# MySens-GWeasySensRS485-V01-045.net
KiCad netlist of a schematic drawn in EAGLE
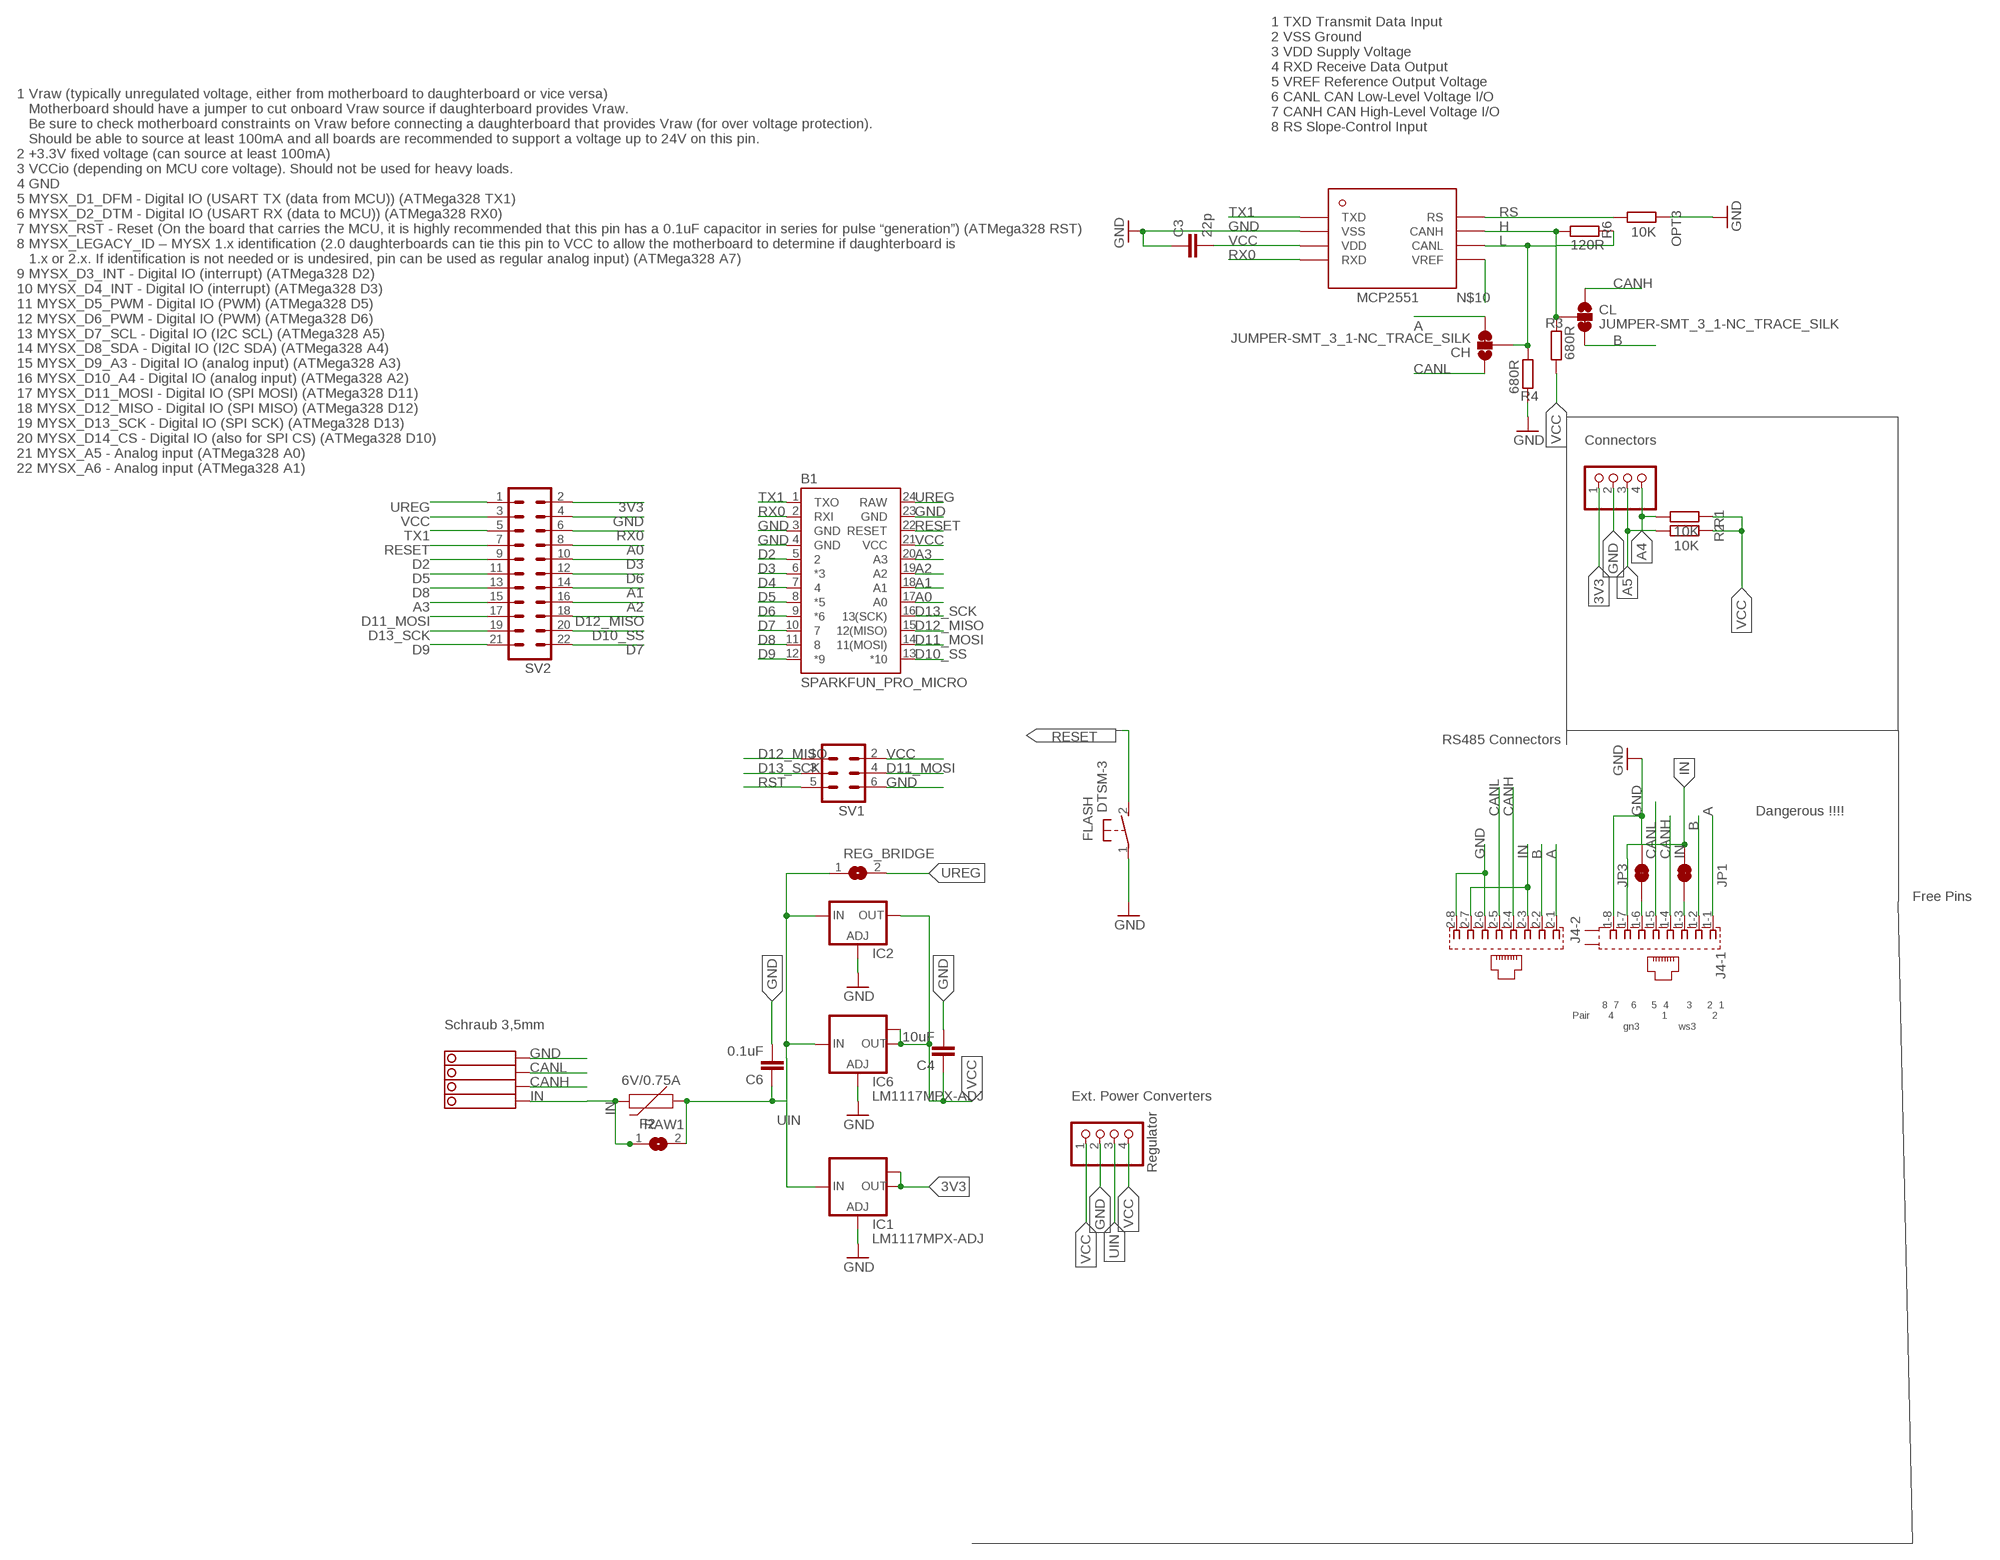
[diagram p0: schematic, sheet 1]

(export (version "E")
  (design (tool "Eeschema 10.0.6"))
  (components
    (comp (ref "B1")
      (value "SPARKFUN_PRO_MICRO")
      (footprint "eagle-import:SPARKFUN_PRO_MICRO")
      (libsource (lib "eagle-import") (part "SPARKFUN_PRO_MICRO"))
    )
    (comp (ref "C3")
      (value "22p")
      (footprint "eagle-import:C0805")
      (libsource (lib "eagle-import") (part "C-EUC0805"))
    )
    (comp (ref "C4")
      (value "10uF")
      (footprint "eagle-import:C1210")
      (libsource (lib "eagle-import") (part "C-EUC1210"))
    )
    (comp (ref "C6")
      (value "0.1uF")
      (footprint "eagle-import:C1206")
      (libsource (lib "eagle-import") (part "C-EUC1206"))
    )
    (comp (ref "CH")
      (value "JUMPER-SMT_3_1-NC_TRACE_SILK")
      (footprint "eagle-import:SMT-JUMPER_3_1-NC_TRACE_SILK")
      (libsource (lib "eagle-import") (part "JUMPER-SMT_3_1-NC_TRACE_SILK"))
    )
    (comp (ref "CL")
      (value "JUMPER-SMT_3_1-NC_TRACE_SILK")
      (footprint "eagle-import:SMT-JUMPER_3_1-NC_TRACE_SILK")
      (libsource (lib "eagle-import") (part "JUMPER-SMT_3_1-NC_TRACE_SILK"))
    )
    (comp (ref "F2")
      (value "6V/0.75A")
      (footprint "eagle-import:1206")
      (libsource (lib "eagle-import") (part "PPTC_THREE-QUARTER-AMP"))
    )
    (comp (ref "FLASH")
      (value "DTSM-3")
      (footprint "eagle-import:DTSM-3")
      (libsource (lib "eagle-import") (part "DTSM-3"))
    )
    (comp (ref "I2C")
      (value "PINHD-1X04_2.54-S")
      (footprint "eagle-import:1X04-S")
      (libsource (lib "eagle-import") (part "PINHD-1X04_2.54-S"))
    )
    (comp (ref "IC1")
      (value "LM1117MPX-ADJ")
      (footprint "eagle-import:SOT223")
      (libsource (lib "eagle-import") (part "LM1117MPX-ADJ"))
    )
    (comp (ref "IC2")
      (value "LD117ADT50TR")
      (footprint "eagle-import:DPACK")
      (libsource (lib "eagle-import") (part "LD117A?DT50TR"))
    )
    (comp (ref "IC6")
      (value "LM1117MPX-ADJ")
      (footprint "eagle-import:SOT223")
      (libsource (lib "eagle-import") (part "LM1117MPX-ADJ"))
    )
    (comp (ref "J4")
      (value "RJ45_2X_NARROW_SHILDPINS_NOCASE")
      (footprint "eagle-import:RJ45_2X_NARROW_SHILDPINS_NOCASE")
      (libsource (lib "eagle-import") (part "RJ45_2X_NARROW_SHILDPINS_NOCASE"))
    )
    (comp (ref "JP1")
      (value "JUMPER-SMT_2_NC_TRACE_SILK")
      (footprint "eagle-import:SMT-JUMPER_2_NC_TRACE_SILK")
      (libsource (lib "eagle-import") (part "JUMPER-SMT_2_NC_TRACE_SILK"))
    )
    (comp (ref "JP3")
      (value "JUMPER-SMT_2_NC_TRACE_SILK")
      (footprint "eagle-import:SMT-JUMPER_2_NC_TRACE_SILK")
      (libsource (lib "eagle-import") (part "JUMPER-SMT_2_NC_TRACE_SILK"))
    )
    (comp (ref "OPT3")
      (value "10K")
      (footprint "eagle-import:R0805")
      (libsource (lib "eagle-import") (part "R-EU_R0805"))
    )
    (comp (ref "R1")
      (value "10K")
      (footprint "eagle-import:R0805")
      (libsource (lib "eagle-import") (part "R-EU_R0805"))
    )
    (comp (ref "R2")
      (value "10K")
      (footprint "eagle-import:R0805")
      (libsource (lib "eagle-import") (part "R-EU_R0805"))
    )
    (comp (ref "R3")
      (value "680R")
      (footprint "eagle-import:R0805")
      (libsource (lib "eagle-import") (part "R-EU_R0805"))
    )
    (comp (ref "R4")
      (value "680R")
      (footprint "eagle-import:R0805")
      (libsource (lib "eagle-import") (part "R-EU_R0805"))
    )
    (comp (ref "R6")
      (value "120R")
      (footprint "eagle-import:R0805")
      (libsource (lib "eagle-import") (part "R-EU_R0805"))
    )
    (comp (ref "RAW1")
      (value "SJ")
      (footprint "eagle-import:SJ")
      (libsource (lib "eagle-import") (part "SJ"))
    )
    (comp (ref "REG_BRIDGE")
      (value "SJ")
      (footprint "eagle-import:SJ")
      (libsource (lib "eagle-import") (part "SJ"))
    )
    (comp (ref "STEPDWN")
      (value "PINHD-1X04_2.54-S")
      (footprint "eagle-import:1X04-S")
      (libsource (lib "eagle-import") (part "PINHD-1X04_2.54-S"))
    )
    (comp (ref "SV1")
      (value "MA03-2")
      (footprint "eagle-import:MA03-2")
      (libsource (lib "eagle-import") (part "MA03-2"))
    )
    (comp (ref "SV2")
      (value "MA11-2")
      (footprint "eagle-import:MA11-2")
      (libsource (lib "eagle-import") (part "MA11-2"))
    )
    (comp (ref "U$1")
      (value "MCP2551")
      (footprint "eagle-import:SOIC-8")
      (libsource (lib "eagle-import") (part "MCP2551"))
    )
    (comp (ref "X4")
      (value "1751264")
      (footprint "eagle-import:1751264")
      (libsource (lib "eagle-import") (part "1751264"))
    )
  )
  (nets
    (net (code "1") (name "/A") (class "Default")
      (node (ref "CH") (pin "3") (pinfunction "3_3") (pintype "passive"))
      (node (ref "J4") (pin "1-1") (pinfunction "1_1-1") (pintype "passive"))
      (node (ref "J4") (pin "2-1") (pinfunction "1_2-1") (pintype "passive"))
    )
    (net (code "2") (name "/A0") (class "Default")
      (node (ref "B1") (pin "17") (pinfunction "A0_17") (pintype "bidirectional"))
      (node (ref "SV2") (pin "8") (pinfunction "8_8") (pintype "passive"))
    )
    (net (code "3") (name "/A1") (class "Default")
      (node (ref "B1") (pin "18") (pinfunction "A1_18") (pintype "bidirectional"))
      (node (ref "SV2") (pin "14") (pinfunction "14_14") (pintype "passive"))
    )
    (net (code "4") (name "/A2") (class "Default")
      (node (ref "B1") (pin "19") (pinfunction "A2_19") (pintype "bidirectional"))
      (node (ref "SV2") (pin "16") (pinfunction "16_16") (pintype "passive"))
    )
    (net (code "5") (name "/A3") (class "Default")
      (node (ref "B1") (pin "20") (pinfunction "A3_20") (pintype "bidirectional"))
      (node (ref "SV2") (pin "15") (pinfunction "15_15") (pintype "passive"))
    )
    (net (code "6") (name "/B") (class "Default")
      (node (ref "CL") (pin "3") (pinfunction "3_3") (pintype "passive"))
      (node (ref "J4") (pin "1-2") (pinfunction "2_1-2") (pintype "passive"))
      (node (ref "J4") (pin "2-2") (pinfunction "2_2-2") (pintype "passive"))
    )
    (net (code "7") (name "/CANH") (class "Default")
      (node (ref "CL") (pin "1") (pinfunction "1_1") (pintype "passive"))
      (node (ref "J4") (pin "1-4") (pinfunction "4_1-4") (pintype "passive"))
      (node (ref "J4") (pin "2-4") (pinfunction "4_2-4") (pintype "passive"))
      (node (ref "X4") (pin "2") (pinfunction "K_2") (pintype "passive"))
    )
    (net (code "8") (name "/CANL") (class "Default")
      (node (ref "CH") (pin "1") (pinfunction "1_1") (pintype "passive"))
      (node (ref "J4") (pin "1-5") (pinfunction "5_1-5") (pintype "passive"))
      (node (ref "J4") (pin "2-5") (pinfunction "5_2-5") (pintype "passive"))
      (node (ref "X4") (pin "3") (pinfunction "K_3") (pintype "passive"))
    )
    (net (code "9") (name "/D2") (class "Default")
      (node (ref "B1") (pin "5") (pinfunction "2_5") (pintype "bidirectional"))
      (node (ref "SV2") (pin "9") (pinfunction "9_9") (pintype "passive"))
    )
    (net (code "10") (name "/D3") (class "Default")
      (node (ref "B1") (pin "6") (pinfunction "*3_6") (pintype "bidirectional"))
      (node (ref "SV2") (pin "10") (pinfunction "10_10") (pintype "passive"))
    )
    (net (code "11") (name "/D4") (class "Default")
      (node (ref "B1") (pin "7") (pinfunction "4_7") (pintype "bidirectional"))
    )
    (net (code "12") (name "/D5") (class "Default")
      (node (ref "B1") (pin "8") (pinfunction "*5_8") (pintype "bidirectional"))
      (node (ref "SV2") (pin "11") (pinfunction "11_11") (pintype "passive"))
    )
    (net (code "13") (name "/D6") (class "Default")
      (node (ref "B1") (pin "9") (pinfunction "*6_9") (pintype "bidirectional"))
      (node (ref "SV2") (pin "12") (pinfunction "12_12") (pintype "passive"))
    )
    (net (code "14") (name "/D7") (class "Default")
      (node (ref "B1") (pin "10") (pinfunction "7_10") (pintype "bidirectional"))
      (node (ref "SV2") (pin "22") (pinfunction "22_22") (pintype "passive"))
    )
    (net (code "15") (name "/D8") (class "Default")
      (node (ref "B1") (pin "11") (pinfunction "8_11") (pintype "bidirectional"))
      (node (ref "SV2") (pin "13") (pinfunction "13_13") (pintype "passive"))
    )
    (net (code "16") (name "/D9") (class "Default")
      (node (ref "B1") (pin "12") (pinfunction "*9_12") (pintype "bidirectional"))
      (node (ref "SV2") (pin "21") (pinfunction "21_21") (pintype "passive"))
    )
    (net (code "17") (name "/D10_SS") (class "Default")
      (node (ref "B1") (pin "13") (pinfunction "*10_13") (pintype "bidirectional"))
      (node (ref "SV2") (pin "20") (pinfunction "20_20") (pintype "passive"))
    )
    (net (code "18") (name "/D11_MOSI") (class "Default")
      (node (ref "B1") (pin "14") (pinfunction "11(MOSI)_14") (pintype "bidirectional"))
      (node (ref "SV1") (pin "4") (pinfunction "4_4") (pintype "passive"))
      (node (ref "SV2") (pin "17") (pinfunction "17_17") (pintype "passive"))
    )
    (net (code "19") (name "/D12_MISO") (class "Default")
      (node (ref "B1") (pin "15") (pinfunction "12(MISO)_15") (pintype "bidirectional"))
      (node (ref "SV1") (pin "1") (pinfunction "1_1") (pintype "passive"))
      (node (ref "SV2") (pin "18") (pinfunction "18_18") (pintype "passive"))
    )
    (net (code "20") (name "/D13_SCK") (class "Default")
      (node (ref "B1") (pin "16") (pinfunction "13(SCK)_16") (pintype "bidirectional"))
      (node (ref "SV1") (pin "3") (pinfunction "3_3") (pintype "passive"))
      (node (ref "SV2") (pin "19") (pinfunction "19_19") (pintype "passive"))
    )
    (net (code "21") (name "/H") (class "Default")
      (node (ref "CL") (pin "2") (pinfunction "2_2") (pintype "passive"))
      (node (ref "R3") (pin "2") (pinfunction "2_2") (pintype "passive"))
      (node (ref "R6") (pin "1") (pinfunction "1_1") (pintype "passive"))
      (node (ref "U$1") (pin "CANH") (pinfunction "CANH_CANH") (pintype "bidirectional"))
    )
    (net (code "22") (name "/L") (class "Default")
      (node (ref "CH") (pin "2") (pinfunction "2_2") (pintype "passive"))
      (node (ref "R4") (pin "1") (pinfunction "1_1") (pintype "passive"))
      (node (ref "R6") (pin "2") (pinfunction "2_2") (pintype "passive"))
      (node (ref "U$1") (pin "CANL") (pinfunction "CANL_CANL") (pintype "bidirectional"))
    )
    (net (code "23") (name "/N$10") (class "Default")
      (node (ref "U$1") (pin "VREF") (pinfunction "VREF_VREF") (pintype "bidirectional"))
    )
    (net (code "24") (name "/RESET") (class "Default")
      (node (ref "B1") (pin "22") (pinfunction "RESET_22") (pintype "bidirectional"))
      (node (ref "FLASH") (pin "2") (pinfunction "2_2") (pintype "passive"))
      (node (ref "SV2") (pin "7") (pinfunction "7_7") (pintype "passive"))
    )
    (net (code "25") (name "/RS") (class "Default")
      (node (ref "OPT3") (pin "2") (pinfunction "2_2") (pintype "passive"))
      (node (ref "U$1") (pin "RS") (pinfunction "RS_RS") (pintype "bidirectional"))
    )
    (net (code "26") (name "/RST") (class "Default")
      (node (ref "SV1") (pin "5") (pinfunction "5_5") (pintype "passive"))
    )
    (net (code "27") (name "/RX0") (class "Default")
      (node (ref "B1") (pin "2") (pinfunction "RXI_2") (pintype "bidirectional"))
      (node (ref "SV2") (pin "6") (pinfunction "6_6") (pintype "passive"))
      (node (ref "U$1") (pin "RXD") (pinfunction "RXD_RXD") (pintype "bidirectional"))
    )
    (net (code "28") (name "/TX1") (class "Default")
      (node (ref "B1") (pin "1") (pinfunction "TXO_1") (pintype "bidirectional"))
      (node (ref "SV2") (pin "5") (pinfunction "5_5") (pintype "passive"))
      (node (ref "U$1") (pin "TXD") (pinfunction "TXD_TXD") (pintype "bidirectional"))
    )
    (net (code "29") (name "3V3") (class "Default")
      (node (ref "I2C") (pin "1") (pinfunction "1_1") (pintype "passive"))
      (node (ref "IC1") (pin "2") (pinfunction "OUT_2") (pintype "passive"))
      (node (ref "IC1") (pin "TAB") (pinfunction "OUT1_TAB") (pintype "passive"))
      (node (ref "SV2") (pin "2") (pinfunction "2_2") (pintype "passive"))
    )
    (net (code "30") (name "A4") (class "Default")
      (node (ref "I2C") (pin "4") (pinfunction "4_4") (pintype "passive"))
      (node (ref "R1") (pin "2") (pinfunction "2_2") (pintype "passive"))
    )
    (net (code "31") (name "A5") (class "Default")
      (node (ref "I2C") (pin "3") (pinfunction "3_3") (pintype "passive"))
      (node (ref "R2") (pin "2") (pinfunction "2_2") (pintype "passive"))
    )
    (net (code "32") (name "GND") (class "Default")
      (node (ref "B1") (pin "23") (pinfunction "GND_23") (pintype "power_in"))
      (node (ref "B1") (pin "3") (pinfunction "GND_3") (pintype "power_in"))
      (node (ref "B1") (pin "4") (pinfunction "GND_4") (pintype "power_in"))
      (node (ref "C3") (pin "1") (pinfunction "1_1") (pintype "passive"))
      (node (ref "C4") (pin "2") (pinfunction "2_2") (pintype "passive"))
      (node (ref "C6") (pin "2") (pinfunction "2_2") (pintype "passive"))
      (node (ref "FLASH") (pin "1") (pinfunction "1_1") (pintype "passive"))
      (node (ref "I2C") (pin "2") (pinfunction "2_2") (pintype "passive"))
      (node (ref "IC1") (pin "1") (pinfunction "ADJ_1") (pintype "input"))
      (node (ref "IC2") (pin "1") (pinfunction "ADJ_1") (pintype "input"))
      (node (ref "IC6") (pin "1") (pinfunction "ADJ_1") (pintype "input"))
      (node (ref "J4") (pin "1-8") (pinfunction "8_1-8") (pintype "passive"))
      (node (ref "J4") (pin "2-6") (pinfunction "6_2-6") (pintype "passive"))
      (node (ref "J4") (pin "2-8") (pinfunction "8_2-8") (pintype "passive"))
      (node (ref "JP3") (pin "2") (pinfunction "2_2") (pintype "passive"))
      (node (ref "OPT3") (pin "1") (pinfunction "1_1") (pintype "passive"))
      (node (ref "R4") (pin "2") (pinfunction "2_2") (pintype "passive"))
      (node (ref "STEPDWN") (pin "2") (pinfunction "2_2") (pintype "passive"))
      (node (ref "SV1") (pin "6") (pinfunction "6_6") (pintype "passive"))
      (node (ref "SV2") (pin "4") (pinfunction "4_4") (pintype "passive"))
      (node (ref "U$1") (pin "VSS") (pinfunction "VSS_VSS") (pintype "bidirectional"))
      (node (ref "X4") (pin "4") (pinfunction "K_4") (pintype "passive"))
    )
    (net (code "33") (name "IN") (class "Default")
      (node (ref "F2") (pin "2") (pinfunction "2_2") (pintype "bidirectional"))
      (node (ref "J4") (pin "1-7") (pinfunction "7_1-7") (pintype "passive"))
      (node (ref "J4") (pin "2-3") (pinfunction "3_2-3") (pintype "passive"))
      (node (ref "J4") (pin "2-7") (pinfunction "7_2-7") (pintype "passive"))
      (node (ref "JP1") (pin "2") (pinfunction "2_2") (pintype "passive"))
      (node (ref "RAW1") (pin "1") (pinfunction "1_1") (pintype "passive"))
      (node (ref "X4") (pin "1") (pinfunction "K_1") (pintype "passive"))
    )
    (net (code "34") (name "Net-(J4A-3)") (class "Default")
      (node (ref "J4") (pin "1-3") (pinfunction "3_1-3") (pintype "passive"))
      (node (ref "JP1") (pin "1") (pinfunction "1_1") (pintype "passive"))
    )
    (net (code "35") (name "Net-(J4A-6)") (class "Default")
      (node (ref "J4") (pin "1-6") (pinfunction "6_1-6") (pintype "passive"))
      (node (ref "JP3") (pin "1") (pinfunction "1_1") (pintype "passive"))
    )
    (net (code "36") (name "UIN") (class "Default")
      (node (ref "C6") (pin "1") (pinfunction "1_1") (pintype "passive"))
      (node (ref "F2") (pin "1") (pinfunction "1_1") (pintype "bidirectional"))
      (node (ref "IC1") (pin "3") (pinfunction "IN_3") (pintype "input"))
      (node (ref "IC2") (pin "3") (pinfunction "IN_3") (pintype "input"))
      (node (ref "IC6") (pin "3") (pinfunction "IN_3") (pintype "input"))
      (node (ref "RAW1") (pin "2") (pinfunction "2_2") (pintype "passive"))
      (node (ref "REG_BRIDGE") (pin "1") (pinfunction "1_1") (pintype "passive"))
      (node (ref "STEPDWN") (pin "3") (pinfunction "3_3") (pintype "passive"))
    )
    (net (code "37") (name "UREG") (class "Default")
      (node (ref "B1") (pin "24") (pinfunction "RAW_24") (pintype "power_in"))
      (node (ref "REG_BRIDGE") (pin "2") (pinfunction "2_2") (pintype "passive"))
      (node (ref "SV2") (pin "1") (pinfunction "1_1") (pintype "passive"))
    )
    (net (code "38") (name "VCC") (class "Default")
      (node (ref "B1") (pin "21") (pinfunction "VCC_21") (pintype "power_in"))
      (node (ref "C3") (pin "2") (pinfunction "2_2") (pintype "passive"))
      (node (ref "C4") (pin "1") (pinfunction "1_1") (pintype "passive"))
      (node (ref "IC2") (pin "4") (pinfunction "OUT_4") (pintype "passive"))
      (node (ref "IC6") (pin "2") (pinfunction "OUT_2") (pintype "passive"))
      (node (ref "IC6") (pin "TAB") (pinfunction "OUT1_TAB") (pintype "passive"))
      (node (ref "R1") (pin "1") (pinfunction "1_1") (pintype "passive"))
      (node (ref "R2") (pin "1") (pinfunction "1_1") (pintype "passive"))
      (node (ref "R3") (pin "1") (pinfunction "1_1") (pintype "passive"))
      (node (ref "STEPDWN") (pin "1") (pinfunction "1_1") (pintype "passive"))
      (node (ref "STEPDWN") (pin "4") (pinfunction "4_4") (pintype "passive"))
      (node (ref "SV1") (pin "2") (pinfunction "2_2") (pintype "passive"))
      (node (ref "SV2") (pin "3") (pinfunction "3_3") (pintype "passive"))
      (node (ref "U$1") (pin "VDD") (pinfunction "VDD_VDD") (pintype "bidirectional"))
    )
    (net (code "39") (name "unconnected-(J4A-S1-PadG1)") (class "Default")
      (node (ref "J4") (pin "G1") (pinfunction "S1_G1") (pintype "passive"))
    )
    (net (code "40") (name "unconnected-(J4A-S2-PadG3)") (class "Default")
      (node (ref "J4") (pin "G3") (pinfunction "S2_G3") (pintype "passive"))
    )
  )
)
